# GPS.net
KiCad netlist of a schematic drawn in Altium Designer
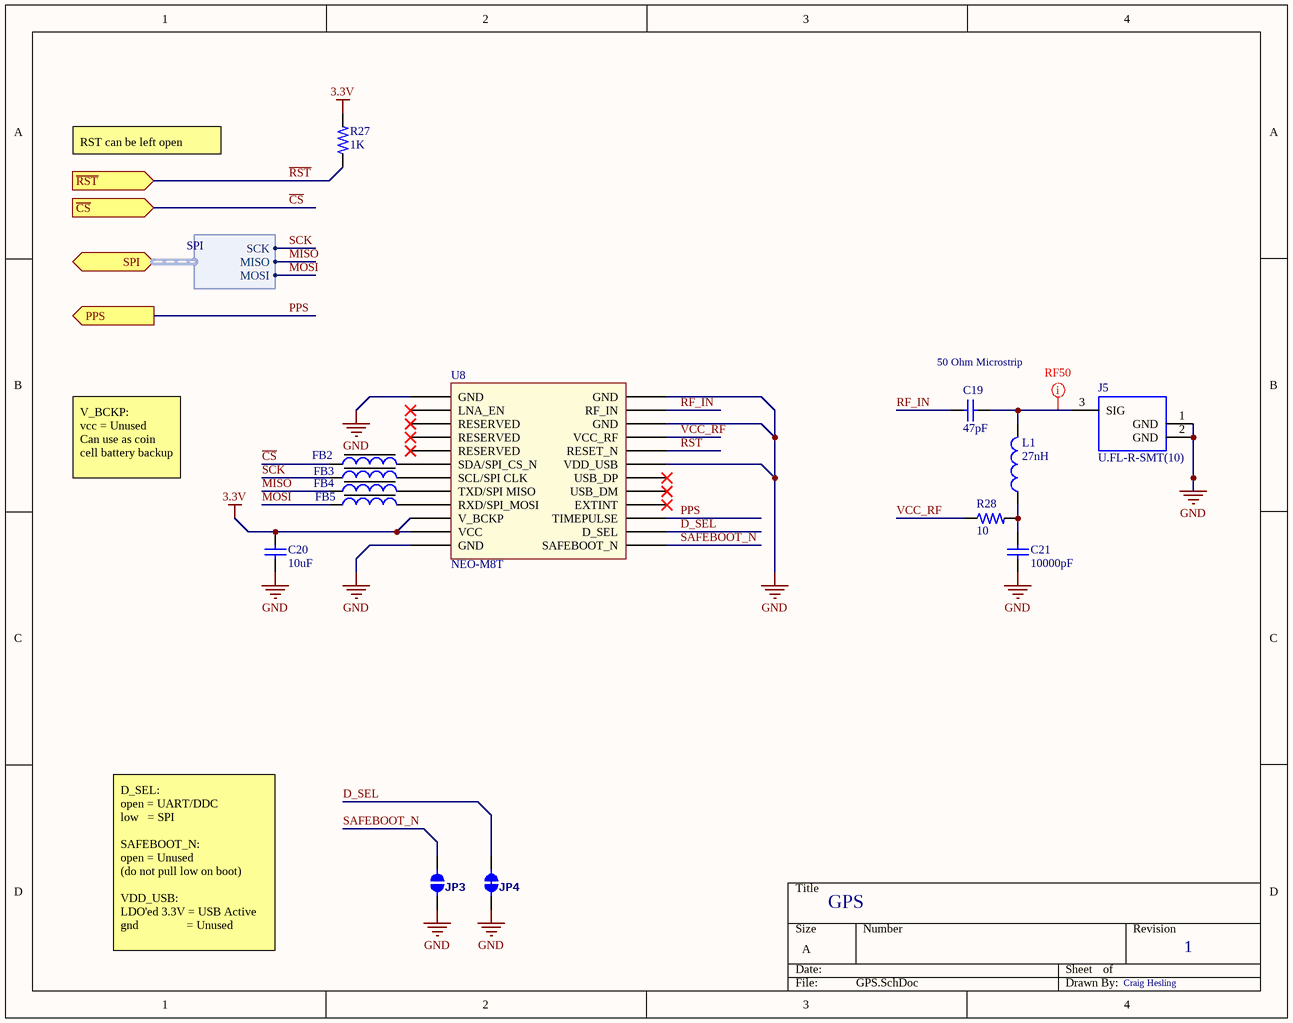
[diagram p0: GPS.SchDoc]

(export (version "E")
  (design (tool "Eeschema 10.0.6"))
  (components
    (comp (ref "C19")
      (value "47pF")
      (footprint "CAPC1608X09L - CAP0603")
      (description "SMT 0603 Ceramic Capacitor")
      (fields (field (name "TOLERANCE") "5%") (field (name "VOLTAGE") "50V"))
      (libsource (lib "Passives") (part "CAP0603 47pF 5% 50V NP0"))
    )
    (comp (ref "C20")
      (value "10uF")
      (footprint "CAPC2013X14L - CAP0805 1.45mm Tall")
      (description "SMT 0805 Ceramic Capacitor")
      (fields (field (name "TOLERANCE") "10%") (field (name "VOLTAGE") "6.3V"))
      (libsource (lib "Passives") (part "CAP0805 10uF 10% 6.3V X5R"))
    )
    (comp (ref "C21")
      (value "10000pF")
      (footprint "CAPC1608X09L - CAP0603")
      (description "SMT 0603 Ceramic Capacitor")
      (fields (field (name "TOLERANCE") "10%") (field (name "VOLTAGE") "50V"))
      (libsource (lib "Passives") (part "CAP0603 10000pF 10% 50V X7R"))
    )
    (comp (ref "FB2")
      (value "Feritte Bead 1kOhm")
      (footprint "FB1608X09L")
      (libsource (lib "Passives") (part "FB0603 1kOhm"))
    )
    (comp (ref "FB3")
      (value "Feritte Bead 1kOhm")
      (footprint "FB1608X09L")
      (libsource (lib "Passives") (part "FB0603 1kOhm"))
    )
    (comp (ref "FB4")
      (value "Feritte Bead 1kOhm")
      (footprint "FB1608X09L")
      (libsource (lib "Passives") (part "FB0603 1kOhm"))
    )
    (comp (ref "FB5")
      (value "Feritte Bead 1kOhm")
      (footprint "FB1608X09L")
      (libsource (lib "Passives") (part "FB0603 1kOhm"))
    )
    (comp (ref "J5")
      (value "U.FL-R-SMT(10)")
      (footprint "HRS-U.FL-R-SMT_V")
      (libsource (lib "Altium Content Vault") (part "HRS-U.FL-R-SMT-3"))
    )
    (comp (ref "JP3")
      (value "JUMPER-PAD-2-NO")
      (footprint "PAD-JUMPER-2-NO_NO_SILK")
      (libsource (lib "Passives") (part "JUMPER-PAD-2-NO"))
    )
    (comp (ref "JP4")
      (value "JUMPER-PAD-2-NC_BY_TRACENO_SILK")
      (footprint "PAD-JUMPER-2-NC_BY_TRACE_NO_SILK")
      (libsource (lib "Passives") (part "JUMPER-PAD-2-NC_BY_TRACENO_SILK"))
    )
    (comp (ref "L1")
      (value "27nH")
      (footprint "INDC1608X09L - IND0603 0.95MM TALL")
      (description "SMT 0603 Ceramic Inductor")
      (fields (field (name "TOLERANCE") "5%"))
      (libsource (lib "Passives") (part "IND0603 27nH 400mA 5% 650mOhm 1.7GHz"))
    )
    (comp (ref "R27")
      (value "1K")
      (footprint "RESC1608X06L - RES0603")
      (description "SMT 0603 Ceramic Resistor")
      (fields (field (name "POWER") "1/10W") (field (name "TOLERANCE") "1%"))
      (libsource (lib "Passives") (part "RES0603 1K 1% 1/10W"))
    )
    (comp (ref "R28")
      (value "10")
      (footprint "RESC1608X06L - RES0603")
      (description "SMT 0603 Ceramic Resistor")
      (fields (field (name "POWER") "1/10W") (field (name "TOLERANCE") "1%"))
      (libsource (lib "Passives") (part "RES0603 10 1% 1/10W"))
    )
    (comp (ref "U8")
      (value "NEO-M8T")
      (footprint "NEO")
      (description "u-blox NEO GNSS module")
      (fields (field (name "MANUFACTURER") "u-blox"))
      (libsource (lib "ubloxLib") (part "NEO"))
    )
  )
  (nets
    (net (code "2") (name "/D_SEL") (class "Default")
      (node (ref "JP4") (pin "2") (pinfunction "2_2") (pintype "passive"))
      (node (ref "U8") (pin "2") (pinfunction "D_SEL_2") (pintype "passive"))
    )
    (net (code "3") (name "/MISO") (class "Default")
      (node (ref "FB4") (pin "1") (pinfunction "1_1") (pintype "passive"))
    )
    (net (code "4") (name "/MOSI") (class "Default")
      (node (ref "FB5") (pin "1") (pinfunction "1_1") (pintype "passive"))
    )
    (net (code "5") (name "/PPS") (class "Default")
      (node (ref "U8") (pin "3") (pinfunction "TIMEPULSE_3") (pintype "passive"))
    )
    (net (code "6") (name "/RF_IN") (class "Default")
      (node (ref "C19") (pin "1") (pinfunction "1_1") (pintype "passive"))
      (node (ref "U8") (pin "11") (pinfunction "RF_IN_11") (pintype "passive"))
    )
    (net (code "7") (name "/SAFEBOOT_N") (class "Default")
      (node (ref "JP3") (pin "2") (pinfunction "2_2") (pintype "passive"))
      (node (ref "U8") (pin "1") (pinfunction "SAFEBOOT_N_1") (pintype "passive"))
    )
    (net (code "8") (name "/SCK") (class "Default")
      (node (ref "FB3") (pin "1") (pinfunction "1_1") (pintype "passive"))
    )
    (net (code "9") (name "/VCC_RF") (class "Default")
      (node (ref "R28") (pin "1") (pinfunction "1_1") (pintype "passive"))
      (node (ref "U8") (pin "9") (pinfunction "VCC_RF_9") (pintype "passive"))
    )
    (net (code "11") (name "/~{CS}") (class "Default")
      (node (ref "FB2") (pin "1") (pinfunction "1_1") (pintype "passive"))
    )
    (net (code "12") (name "/~{RST}") (class "Default")
      (node (ref "R27") (pin "1") (pinfunction "1_1") (pintype "passive"))
      (node (ref "U8") (pin "8") (pinfunction "RESET_N_8") (pintype "passive"))
    )
    (net (code "13") (name "3.3V") (class "Default")
      (node (ref "C20") (pin "2") (pinfunction "2_2") (pintype "passive"))
      (node (ref "R27") (pin "2") (pinfunction "2_2") (pintype "passive"))
      (node (ref "U8") (pin "22") (pinfunction "V_BCKP_22") (pintype "passive"))
      (node (ref "U8") (pin "23") (pinfunction "VCC_23") (pintype "passive"))
    )
    (net (code "14") (name "GND") (class "Default")
      (node (ref "C20") (pin "1") (pinfunction "1_1") (pintype "passive"))
      (node (ref "C21") (pin "1") (pinfunction "1_1") (pintype "passive"))
      (node (ref "J5") (pin "1") (pinfunction "GND_1") (pintype "power_in"))
      (node (ref "J5") (pin "2") (pinfunction "GND_2") (pintype "power_in"))
      (node (ref "JP3") (pin "1") (pinfunction "1_1") (pintype "passive"))
      (node (ref "JP4") (pin "1") (pinfunction "1_1") (pintype "passive"))
      (node (ref "U8") (pin "10") (pinfunction "GND_10") (pintype "passive"))
      (node (ref "U8") (pin "12") (pinfunction "GND_12") (pintype "passive"))
      (node (ref "U8") (pin "13") (pinfunction "GND_13") (pintype "passive"))
      (node (ref "U8") (pin "24") (pinfunction "GND_24") (pintype "passive"))
      (node (ref "U8") (pin "7") (pinfunction "VDD_USB_7") (pintype "passive"))
    )
    (net (code "15") (name "Net-(C21-Pad2)") (class "Default")
      (node (ref "C21") (pin "2") (pinfunction "2_2") (pintype "passive"))
      (node (ref "L1") (pin "1") (pinfunction "1_1") (pintype "passive"))
      (node (ref "R28") (pin "2") (pinfunction "2_2") (pintype "passive"))
    )
    (net (code "16") (name "Net-(J5-SIG)") (class "Default")
      (node (ref "C19") (pin "2") (pinfunction "2_2") (pintype "passive"))
      (node (ref "J5") (pin "3") (pinfunction "SIG_3") (pintype "passive"))
      (node (ref "L1") (pin "2") (pinfunction "2_2") (pintype "passive"))
    )
    (net (code "17") (name "Net-(U8-RXD{slash}SPI_MOSI)") (class "Default")
      (node (ref "FB5") (pin "2") (pinfunction "2_2") (pintype "passive"))
      (node (ref "U8") (pin "21") (pinfunction "RXD/SPI_MOSI_21") (pintype "passive"))
    )
    (net (code "18") (name "Net-(U8-SCL{slash}SPI_CLK)") (class "Default")
      (node (ref "FB3") (pin "2") (pinfunction "2_2") (pintype "passive"))
      (node (ref "U8") (pin "19") (pinfunction "SCL/SPI_CLK_19") (pintype "passive"))
    )
    (net (code "19") (name "Net-(U8-SDA{slash}SPI_CS_N)") (class "Default")
      (node (ref "FB2") (pin "2") (pinfunction "2_2") (pintype "passive"))
      (node (ref "U8") (pin "18") (pinfunction "SDA/SPI_CS_N_18") (pintype "passive"))
    )
    (net (code "20") (name "Net-(U8-TXD{slash}SPI_MISO)") (class "Default")
      (node (ref "FB4") (pin "2") (pinfunction "2_2") (pintype "passive"))
      (node (ref "U8") (pin "20") (pinfunction "TXD/SPI_MISO_20") (pintype "passive"))
    )
    (net (code "21") (name "unconnected-(U8-EXTINT-Pad4)") (class "Default")
      (node (ref "U8") (pin "4") (pinfunction "EXTINT_4") (pintype "passive+no_connect"))
    )
    (net (code "22") (name "unconnected-(U8-LNA_EN-Pad14)") (class "Default")
      (node (ref "U8") (pin "14") (pinfunction "LNA_EN_14") (pintype "passive+no_connect"))
    )
    (net (code "23") (name "unconnected-(U8-RESERVED-Pad15)") (class "Default")
      (node (ref "U8") (pin "15") (pinfunction "RESERVED_15") (pintype "passive+no_connect"))
    )
    (net (code "24") (name "unconnected-(U8-RESERVED-Pad16)") (class "Default")
      (node (ref "U8") (pin "16") (pinfunction "RESERVED_16") (pintype "passive+no_connect"))
    )
    (net (code "25") (name "unconnected-(U8-RESERVED-Pad17)") (class "Default")
      (node (ref "U8") (pin "17") (pinfunction "RESERVED_17") (pintype "passive+no_connect"))
    )
    (net (code "26") (name "unconnected-(U8-USB_DM-Pad5)") (class "Default")
      (node (ref "U8") (pin "5") (pinfunction "USB_DM_5") (pintype "passive+no_connect"))
    )
    (net (code "27") (name "unconnected-(U8-USB_DP-Pad6)") (class "Default")
      (node (ref "U8") (pin "6") (pinfunction "USB_DP_6") (pintype "passive+no_connect"))
    )
  )
)
